# pcb.net
KiCad netlist of a schematic drawn in EasyEDA
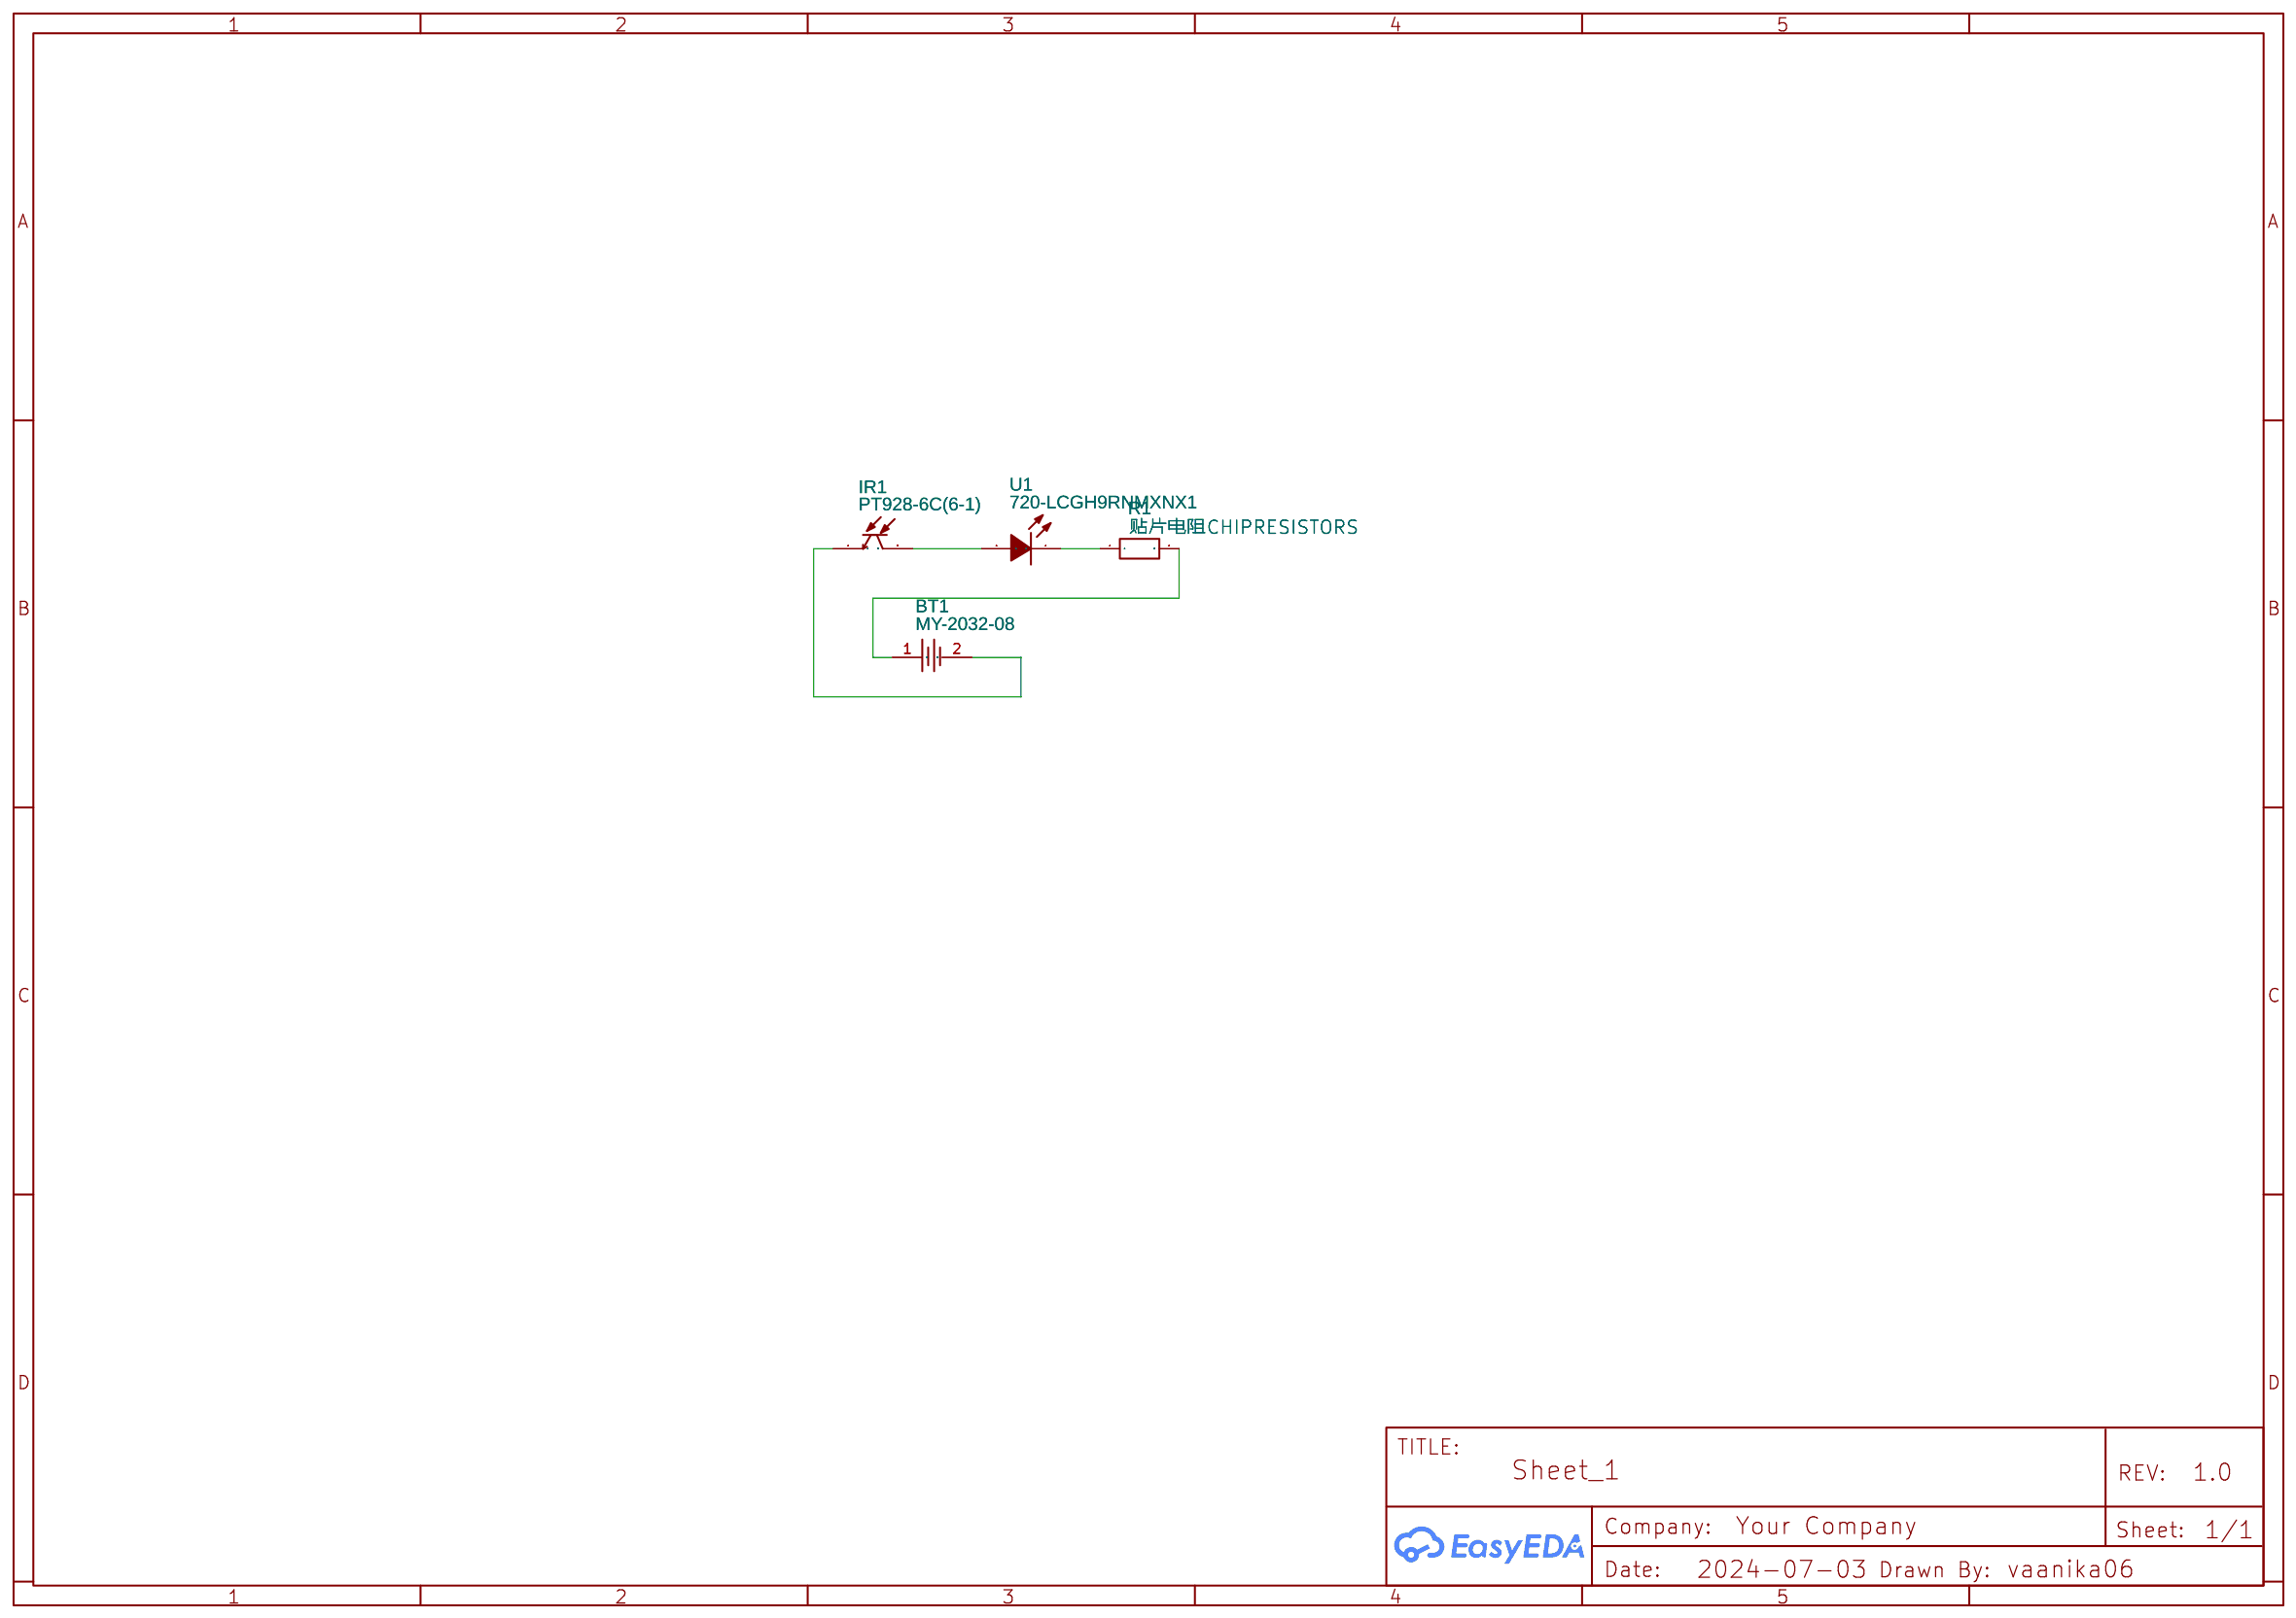
[diagram p0: schematic sheet]

(export (version "E")
  (design (tool "Eeschema 10.0.6"))
  (components
    (comp (ref "BT1")
      (value "MY-2032-08")
      (fields (field (name "Manufacturer") "MYOUNG(美阳)"))
      (libsource (lib "") (part "MY-2032-08"))
    )
    (comp (ref "IR1")
      (value "PT928-6C(6-1)")
      (fields (field (name "Manufacturer") "EVERLIGHT(亿光)"))
      (libsource (lib "") (part "PT928-6C(6-1)"))
    )
    (comp (ref "R1")
      (value "贴片电阻CHIPRESISTORS")
      (fields (field (name "Manufacturer Part") "贴片电阻ChipResistors"))
      (libsource (lib "") (part "贴片电阻CHIPRESISTORS"))
    )
    (comp (ref "U1") (value "720-LCGH9RNMXNX1") (libsource (lib "") (part "720-LCGH9RNMXNX1")))
  )
  (nets
    (net (code "1") (name "Net-(BT1-Pad1)") (class "Default")
      (node (ref "BT1") (pin "1") (pinfunction "1_1") (pintype "input"))
      (node (ref "R1") (pin "2") (pinfunction "2_2") (pintype "unspecified"))
    )
    (net (code "2") (name "Net-(IR1-C)") (class "Default")
      (node (ref "IR1") (pin "2") (pinfunction "C_2") (pintype "input"))
      (node (ref "U1") (pin "2") (pinfunction "A_2") (pintype "unspecified"))
    )
    (net (code "3") (name "Net-(IR1-E)") (class "Default")
      (node (ref "BT1") (pin "2") (pinfunction "2_2") (pintype "input"))
      (node (ref "IR1") (pin "1") (pinfunction "E_1") (pintype "input"))
    )
    (net (code "4") (name "Net-(U1-K)") (class "Default")
      (node (ref "R1") (pin "1") (pinfunction "1_1") (pintype "unspecified"))
      (node (ref "U1") (pin "1") (pinfunction "K_1") (pintype "unspecified"))
    )
  )
)
